# Flyback_Supply.net
KiCad netlist of a schematic drawn in Altium Designer
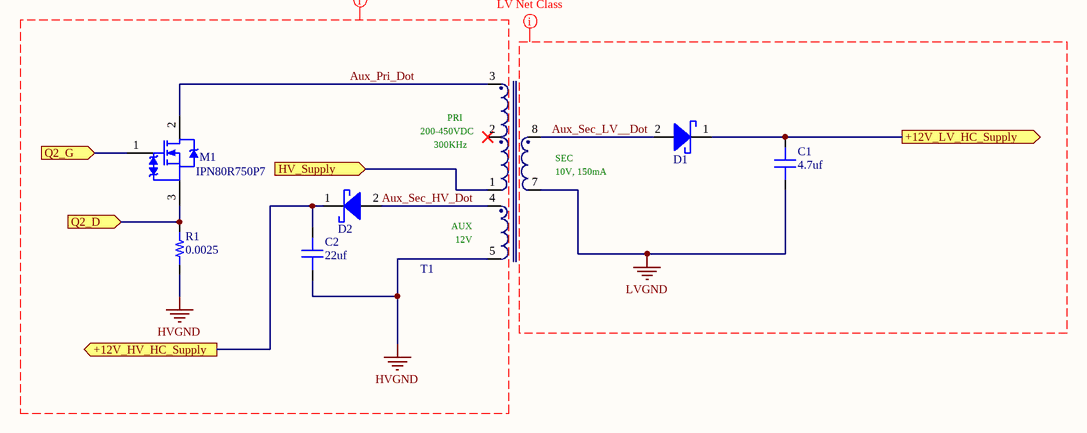
[diagram p0: Flyback Supply.SchDoc]

(export (version "E")
  (design (tool "Eeschema 10.0.6"))
  (components
    (comp (ref "C1")
      (value "4.7uf")
      (footprint "CAP 0805/2012")
      (fields
        (field (name "Comment") "Capacitor MLCC 4.7uf 25V CAP 0805/2012")
        (field (name "CREATED_BY") "Nick Mah")
      )
      (libsource (lib "Altium-Lib") (part "Capacitor"))
    )
    (comp (ref "C2")
      (value "22uf")
      (footprint "CAP 1206/3216 - 1.8MM")
      (fields
        (field (name "Comment") "Capacitor MLCC 22uf 25V CAP 1206/3216")
        (field (name "CREATED_BY") "Nick Mah")
      )
      (libsource (lib "Altium-Lib") (part "Capacitor"))
    )
    (comp (ref "D1")
      (value "BAT46WJ")
      (footprint "SOD323F")
      (description "Diode Schottky 100V 250mA (DC) Surface Mount SOD-323F")
      (fields
        (field (name "POWER") "100Vr")
        (field (name "MFRPARTNO") "BAT46WJ,115")
        (field (name "CREATED_BY") "Nick Mah")
      )
      (libsource (lib "Altium-Lib") (part "Schottky"))
    )
    (comp (ref "D2")
      (value "BAT46WJ")
      (footprint "SOD323F")
      (description "Diode Schottky 100V 250mA (DC) Surface Mount SOD-323F")
      (fields
        (field (name "POWER") "100Vr")
        (field (name "MFRPARTNO") "BAT46WJ,115")
        (field (name "CREATED_BY") "Nick Mah")
      )
      (libsource (lib "Altium-Lib") (part "Schottky"))
    )
    (comp (ref "M1")
      (value "AUX Transistor")
      (footprint "PG-SOT223")
      (description "COOLMOS P7 800V SOT-223")
      (fields
        (field (name "MFRPARTNO") "IPN80R750P7ATMA1")
        (field (name "NAME") "IPN80R750P7")
        (field (name "CREATED_BY") "Nick Mah")
      )
      (libsource (lib "Altium-Lib") (part "IPN80R750P7"))
    )
    (comp (ref "R1")
      (value "0.0025")
      (footprint "RES 0603/1608")
      (fields
        (field (name "TOLERANCE") "1%")
        (field (name "POWER") "1/4W")
        (field (name "MFRPARTNO") "CSRF0603FT2L50")
        (field (name "CREATED_BY") "Nick Mah")
      )
      (libsource (lib "Altium-Lib") (part "Resistor"))
    )
    (comp (ref "T1")
      (value "Aux Transformer")
      (footprint "750817020")
      (description "Auxilliary Transformer for DC-DC Senior Project")
      (fields (field (name "TOLERANCE") "10%") (field (name "MFRPARTNO") "750817020"))
      (libsource (lib "Altium-Lib") (part "750817020"))
    )
  )
  (nets
    (net (code "1") (name "/+12V_HV_HC_Supply") (class "Default")
      (node (ref "C2") (pin "2") (pinfunction "2_2") (pintype "passive"))
      (node (ref "D2") (pin "1") (pinfunction "K_1") (pintype "passive"))
    )
    (net (code "2") (name "/+12V_LV_HC_Supply") (class "Default")
      (node (ref "C1") (pin "2") (pinfunction "2_2") (pintype "passive"))
      (node (ref "D1") (pin "1") (pinfunction "K_1") (pintype "passive"))
    )
    (net (code "3") (name "/Aux_Pri_Dot") (class "Default")
      (node (ref "M1") (pin "2") (pinfunction "D_2") (pintype "passive"))
      (node (ref "T1") (pin "3") (pinfunction "3_3") (pintype "passive"))
    )
    (net (code "4") (name "/Aux_Sec_HV_Dot") (class "Default")
      (node (ref "D2") (pin "2") (pinfunction "A_2") (pintype "passive"))
      (node (ref "T1") (pin "4") (pinfunction "4_4") (pintype "passive"))
    )
    (net (code "5") (name "/Aux_Sec_LV__Dot") (class "Default")
      (node (ref "D1") (pin "2") (pinfunction "A_2") (pintype "passive"))
      (node (ref "T1") (pin "8") (pinfunction "8_8") (pintype "passive"))
    )
    (net (code "6") (name "/HV_Supply") (class "Default")
      (node (ref "T1") (pin "1") (pinfunction "1_1") (pintype "passive"))
    )
    (net (code "7") (name "/Q2_D") (class "Default")
      (node (ref "M1") (pin "3") (pinfunction "S_3") (pintype "passive"))
      (node (ref "R1") (pin "2") (pinfunction "2_2") (pintype "passive"))
    )
    (net (code "8") (name "/Q2_G") (class "Default")
      (node (ref "M1") (pin "1") (pinfunction "G_1") (pintype "passive"))
    )
    (net (code "9") (name "HVGND") (class "Default")
      (node (ref "C2") (pin "1") (pinfunction "1_1") (pintype "passive"))
      (node (ref "R1") (pin "1") (pinfunction "1_1") (pintype "passive"))
      (node (ref "T1") (pin "5") (pinfunction "5_5") (pintype "passive"))
    )
    (net (code "10") (name "LVGND") (class "Default")
      (node (ref "C1") (pin "1") (pinfunction "1_1") (pintype "passive"))
      (node (ref "T1") (pin "7") (pinfunction "7_7") (pintype "passive"))
    )
    (net (code "11") (name "unconnected-(T1-Pad2)") (class "Default")
      (node (ref "T1") (pin "2") (pinfunction "2_2") (pintype "passive+no_connect"))
    )
  )
)
